# 7_-_ADC_Chip.net
KiCad netlist of a schematic drawn in Altium Designer
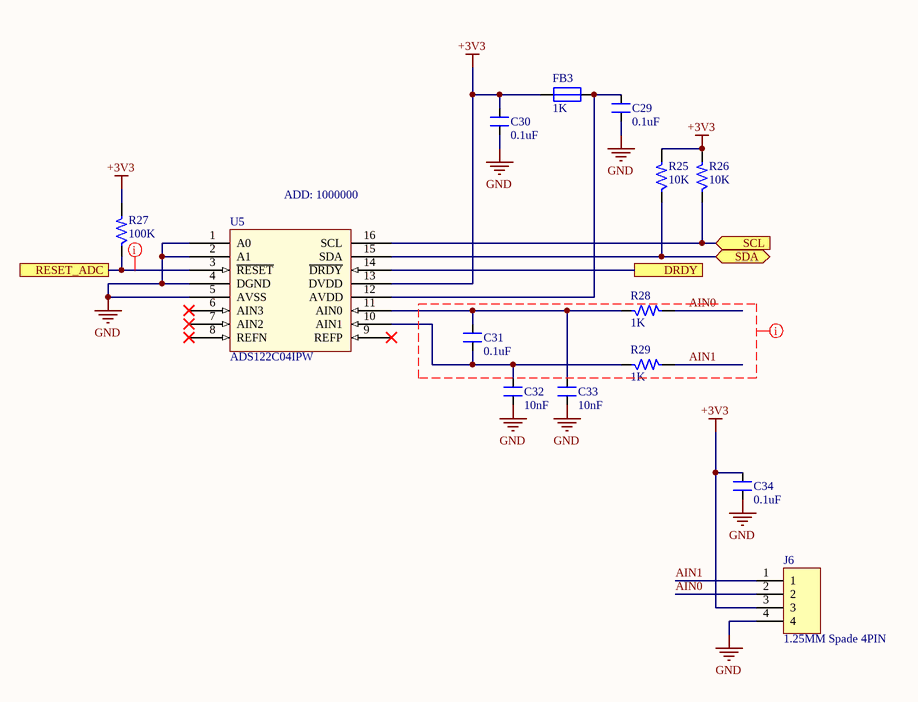
[diagram p0: [7] - ADC Chip.SchDoc]

(export (version "E")
  (design (tool "Eeschema 10.0.6"))
  (components
    (comp (ref "C29")
      (value "0.1uF")
      (footprint "CAP_0805")
      (description "0.1µF ±10% 50V Ceramic Capacitor X7R 0805 (2012 Metric)")
      (fields
        (field (name "MANUFACTURER") "Samsung")
        (field (name "MANUFACTURER PART NUMBER") "CL21B104KBCNNNC")
      )
      (libsource (lib "ESTEEMPCBLIB") (part "CAP_0.1uF-50V-10%-0805"))
    )
    (comp (ref "C30")
      (value "0.1uF")
      (footprint "CAP_0805")
      (description "0.1µF ±10% 50V Ceramic Capacitor X7R 0805 (2012 Metric)")
      (fields
        (field (name "MANUFACTURER") "Samsung")
        (field (name "MANUFACTURER PART NUMBER") "CL21B104KBCNNNC")
      )
      (libsource (lib "ESTEEMPCBLIB") (part "CAP_0.1uF-50V-10%-0805"))
    )
    (comp (ref "C31")
      (value "0.1uF")
      (footprint "CAP_0805")
      (description "0.1µF ±10% 50V Ceramic Capacitor X7R 0805 (2012 Metric)")
      (fields
        (field (name "MANUFACTURER") "Samsung")
        (field (name "MANUFACTURER PART NUMBER") "CL21B104KBCNNNC")
      )
      (libsource (lib "ESTEEMPCBLIB") (part "CAP_0.1uF-50V-10%-0805"))
    )
    (comp (ref "C32")
      (value "10nF")
      (footprint "CAP_0805")
      (description "10000pF ±10% 50V Ceramic Capacitor X7R 0805 (2012 Metric)")
      (fields
        (field (name "MANUFACTURER") "Samsung")
        (field (name "MANUFACTURER PART NUMBER") "C0805C103K5RECAUTO")
      )
      (libsource (lib "ESTEEMPCBLIB") (part "CAP_10nF-50V-10%-0805"))
    )
    (comp (ref "C33")
      (value "10nF")
      (footprint "CAP_0805")
      (description "10000pF ±10% 50V Ceramic Capacitor X7R 0805 (2012 Metric)")
      (fields
        (field (name "MANUFACTURER") "Samsung")
        (field (name "MANUFACTURER PART NUMBER") "C0805C103K5RECAUTO")
      )
      (libsource (lib "ESTEEMPCBLIB") (part "CAP_10nF-50V-10%-0805"))
    )
    (comp (ref "C34")
      (value "0.1uF")
      (footprint "CAP_0805")
      (description "0.1µF ±10% 50V Ceramic Capacitor X7R 0805 (2012 Metric)")
      (fields
        (field (name "MANUFACTURER") "Samsung")
        (field (name "MANUFACTURER PART NUMBER") "CL21B104KBCNNNC")
      )
      (libsource (lib "ESTEEMPCBLIB") (part "CAP_0.1uF-50V-10%-0805"))
    )
    (comp (ref "FB3")
      (value "1K")
      (footprint "IND_0805")
      (description "1 kOhms @ 100MHz 1 Power Line Ferrite Bead 0805 (2012 Metric) 1.6A")
      (fields
        (field (name "MANUFACTURER") "Laird")
        (field (name "MANUFACTURER PART NUMBER") "BLM21SP102SH1D")
      )
      (libsource (lib "ESTEEMPCBLIB") (part "FB_1K-100MHZ-1.6A-0805"))
    )
    (comp (ref "J6")
      (value "1.25MM Spade 4PIN")
      (footprint "CON4_50_653004117322_TH_RA")
      (description "4 Pins, 1 Row 1.25mm Pitch, right angle Connector, male")
      (fields (field (name "MANUFACTURER PART NUMBER") "653004117322") (field (name "MANUFACTURER") "JST"))
      (libsource (lib "ESTEEMPCBLIB") (part "CON-PLG_4X1-50-RA-TH"))
    )
    (comp (ref "R25")
      (value "10K")
      (footprint "RES_0603")
      (description "10 kOhms ±1% 0.1W, 1/10W Chip Resistor 0603 (1608 Metric) Automotive AEC-Q200 Thick Film")
      (fields (field (name "MANUFACTURER") "Walsin") (field (name "MANUFACTURER PART NUMBER") "WR06X1002FTL"))
      (libsource (lib "ESTEEMPCBLIB") (part "RES_10K-0.1W-1%-0603"))
    )
    (comp (ref "R26")
      (value "10K")
      (footprint "RES_0603")
      (description "10 kOhms ±1% 0.1W, 1/10W Chip Resistor 0603 (1608 Metric) Automotive AEC-Q200 Thick Film")
      (fields (field (name "MANUFACTURER") "Walsin") (field (name "MANUFACTURER PART NUMBER") "WR06X1002FTL"))
      (libsource (lib "ESTEEMPCBLIB") (part "RES_10K-0.1W-1%-0603"))
    )
    (comp (ref "R27")
      (value "100K")
      (footprint "RES_0603")
      (description "100 kOhms ±1% 0.1W, 1/10W Chip Resistor 0603 (1608 Metric) Automotive AEC-Q200 Thick Film")
      (fields
        (field (name "MANUFACTURER") "Stackpole Electronics")
        (field (name "MANUFACTURER PART NUMBER") "RMCF0603FT100K")
      )
      (libsource (lib "ESTEEMPCBLIB") (part "RES_100K-0.1W-1%-0603"))
    )
    (comp (ref "R28")
      (value "1K")
      (footprint "RES_0603")
      (description "1 kOhms ±1% 0.1W, 1/10W Chip Resistor 0603 (1608 Metric) Automotive AEC-Q200 Thick Film")
      (fields (field (name "MANUFACTURER") "Walsin") (field (name "MANUFACTURER PART NUMBER") "WR06X1001FTL"))
      (libsource (lib "ESTEEMPCBLIB") (part "RES_1K-0.1W-1%-0603"))
    )
    (comp (ref "R29")
      (value "1K")
      (footprint "RES_0603")
      (description "1 kOhms ±1% 0.1W, 1/10W Chip Resistor 0603 (1608 Metric) Automotive AEC-Q200 Thick Film")
      (fields (field (name "MANUFACTURER") "Walsin") (field (name "MANUFACTURER PART NUMBER") "WR06X1001FTL"))
      (libsource (lib "ESTEEMPCBLIB") (part "RES_1K-0.1W-1%-0603"))
    )
    (comp (ref "U5")
      (value "ADS122C04IPW")
      (footprint "TSSOP16_25-59_294_54X14_SMT")
      (description "24 Bit Analog to Digital Converter 4 Input 1 Sigma-Delta 16-TSSOP")
      (fields (field (name "MANUFACTURER") "Texas Instruments"))
      (libsource (lib "ESTEEMPCBLIB") (part "IC_ADS122C04IPW"))
    )
  )
  (nets
    (net (code "1") (name "+3V3") (class "Default")
      (node (ref "C30") (pin "2") (pinfunction "2_2") (pintype "passive"))
      (node (ref "C34") (pin "2") (pinfunction "2_2") (pintype "passive"))
      (node (ref "FB3") (pin "1") (pinfunction "1_1") (pintype "passive"))
      (node (ref "J6") (pin "3") (pinfunction "3_3") (pintype "passive"))
      (node (ref "R25") (pin "2") (pinfunction "2_2") (pintype "passive"))
      (node (ref "R26") (pin "2") (pinfunction "2_2") (pintype "passive"))
      (node (ref "R27") (pin "2") (pinfunction "2_2") (pintype "passive"))
      (node (ref "U5") (pin "13") (pinfunction "DVDD_13") (pintype "power_in"))
    )
    (net (code "2") (name "/AIN0") (class "Default")
      (node (ref "J6") (pin "2") (pinfunction "2_2") (pintype "passive"))
      (node (ref "R28") (pin "2") (pinfunction "2_2") (pintype "passive"))
    )
    (net (code "3") (name "/AIN1") (class "Default")
      (node (ref "J6") (pin "1") (pinfunction "1_1") (pintype "passive"))
      (node (ref "R29") (pin "2") (pinfunction "2_2") (pintype "passive"))
    )
    (net (code "4") (name "/DRDY") (class "Default")
      (node (ref "U5") (pin "14") (pinfunction "DRDY_14") (pintype "input"))
    )
    (net (code "5") (name "/RESET_ADC") (class "Default")
      (node (ref "R27") (pin "1") (pinfunction "1_1") (pintype "passive"))
      (node (ref "U5") (pin "3") (pinfunction "RESET_3") (pintype "input"))
    )
    (net (code "6") (name "/SCL") (class "Default")
      (node (ref "R26") (pin "1") (pinfunction "1_1") (pintype "passive"))
      (node (ref "U5") (pin "16") (pinfunction "SCL_16") (pintype "open_collector"))
    )
    (net (code "7") (name "/SDA") (class "Default")
      (node (ref "R25") (pin "1") (pinfunction "1_1") (pintype "passive"))
      (node (ref "U5") (pin "15") (pinfunction "SDA_15") (pintype "open_collector"))
    )
    (net (code "8") (name "GND") (class "Default")
      (node (ref "C29") (pin "1") (pinfunction "1_1") (pintype "passive"))
      (node (ref "C30") (pin "1") (pinfunction "1_1") (pintype "passive"))
      (node (ref "C32") (pin "1") (pinfunction "1_1") (pintype "passive"))
      (node (ref "C33") (pin "1") (pinfunction "1_1") (pintype "passive"))
      (node (ref "C34") (pin "1") (pinfunction "1_1") (pintype "passive"))
      (node (ref "J6") (pin "4") (pinfunction "4_4") (pintype "passive"))
      (node (ref "U5") (pin "1") (pinfunction "A0_1") (pintype "passive"))
      (node (ref "U5") (pin "2") (pinfunction "A1_2") (pintype "passive"))
      (node (ref "U5") (pin "4") (pinfunction "DGND_4") (pintype "power_in"))
      (node (ref "U5") (pin "5") (pinfunction "AVSS_5") (pintype "power_in"))
    )
    (net (code "9") (name "Net-(U5-AIN0)") (class "Default")
      (node (ref "C31") (pin "2") (pinfunction "2_2") (pintype "passive"))
      (node (ref "C33") (pin "2") (pinfunction "2_2") (pintype "passive"))
      (node (ref "R28") (pin "1") (pinfunction "1_1") (pintype "passive"))
      (node (ref "U5") (pin "11") (pinfunction "AIN0_11") (pintype "input"))
    )
    (net (code "10") (name "Net-(U5-AIN1)") (class "Default")
      (node (ref "C31") (pin "1") (pinfunction "1_1") (pintype "passive"))
      (node (ref "C32") (pin "2") (pinfunction "2_2") (pintype "passive"))
      (node (ref "R29") (pin "1") (pinfunction "1_1") (pintype "passive"))
      (node (ref "U5") (pin "10") (pinfunction "AIN1_10") (pintype "input"))
    )
    (net (code "11") (name "Net-(U5-AVDD)") (class "Default")
      (node (ref "C29") (pin "2") (pinfunction "2_2") (pintype "passive"))
      (node (ref "FB3") (pin "2") (pinfunction "2_2") (pintype "passive"))
      (node (ref "U5") (pin "12") (pinfunction "AVDD_12") (pintype "power_in"))
    )
    (net (code "12") (name "unconnected-(U5-AIN2-Pad7)") (class "Default")
      (node (ref "U5") (pin "7") (pinfunction "AIN2_7") (pintype "input+no_connect"))
    )
    (net (code "13") (name "unconnected-(U5-AIN3-Pad6)") (class "Default")
      (node (ref "U5") (pin "6") (pinfunction "AIN3_6") (pintype "input+no_connect"))
    )
    (net (code "14") (name "unconnected-(U5-REFN-Pad8)") (class "Default")
      (node (ref "U5") (pin "8") (pinfunction "REFN_8") (pintype "input+no_connect"))
    )
    (net (code "15") (name "unconnected-(U5-REFP-Pad9)") (class "Default")
      (node (ref "U5") (pin "9") (pinfunction "REFP_9") (pintype "input+no_connect"))
    )
  )
)
